# PWR.net
KiCad netlist of a schematic drawn in Altium Designer
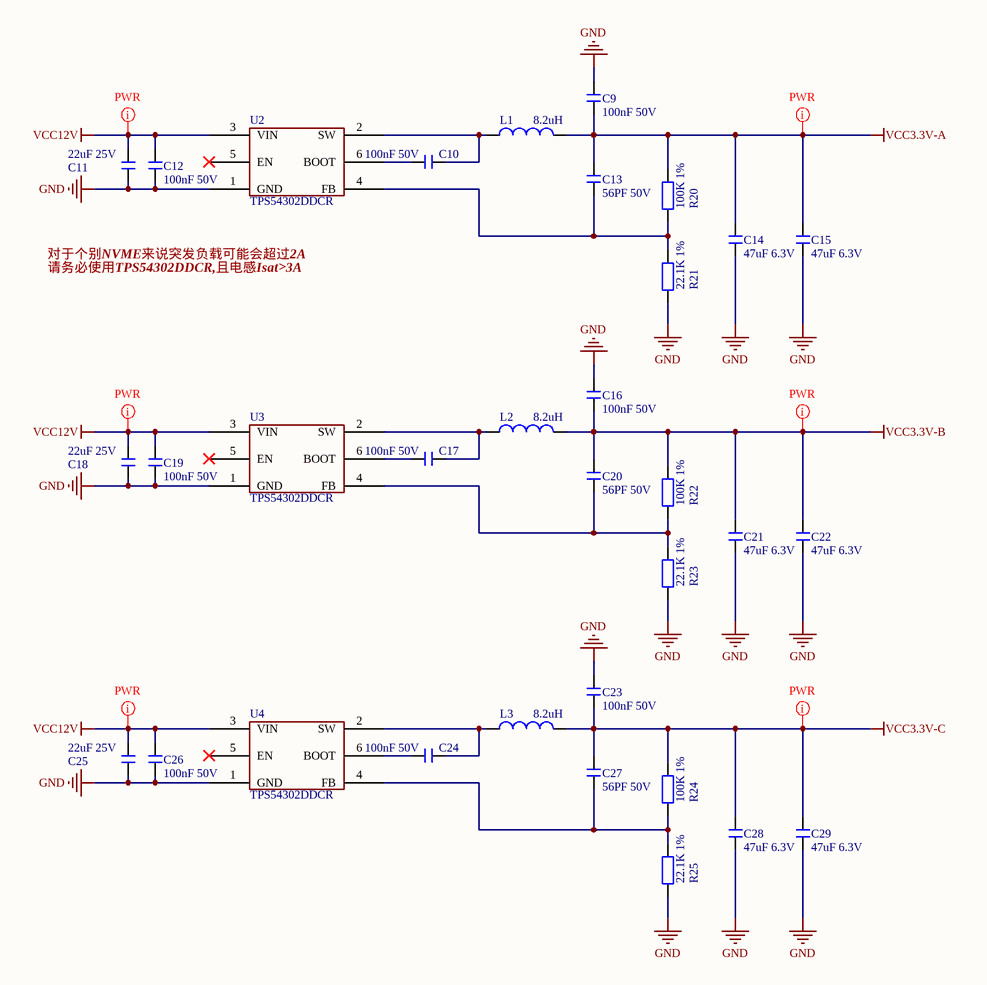
[diagram p0: PWR.SchDoc]

(export (version "E")
  (design (tool "Eeschema 10.0.6"))
  (components
    (comp (ref "C9")
      (value "100nF 50V")
      (footprint "C0402_L")
      (description "无极性贴片电容")
      (fields (field (name "版权归属") "源创客"))
      (libsource (lib "Capacitor") (part "C"))
    )
    (comp (ref "C10")
      (value "100nF 50V")
      (footprint "C0402_L")
      (description "无极性贴片电容")
      (fields (field (name "版权归属") "源创客"))
      (libsource (lib "Capacitor") (part "C"))
    )
    (comp (ref "C11")
      (value "22uF 25V")
      (footprint "C0805_L")
      (description "无极性贴片电容")
      (fields (field (name "版权归属") "源创客"))
      (libsource (lib "Capacitor") (part "C"))
    )
    (comp (ref "C12")
      (value "100nF 50V")
      (footprint "C0402_L")
      (description "无极性贴片电容")
      (fields (field (name "版权归属") "源创客"))
      (libsource (lib "Capacitor") (part "C"))
    )
    (comp (ref "C13")
      (value "56PF 50V")
      (footprint "C0402_L")
      (description "无极性贴片电容")
      (fields (field (name "版权归属") "源创客"))
      (libsource (lib "Capacitor") (part "C"))
    )
    (comp (ref "C14")
      (value "47uF 6.3V")
      (footprint "C0805_L")
      (description "无极性贴片电容")
      (fields (field (name "版权归属") "源创客"))
      (libsource (lib "Capacitor") (part "C"))
    )
    (comp (ref "C15")
      (value "47uF 6.3V")
      (footprint "C0805_L")
      (description "无极性贴片电容")
      (fields (field (name "版权归属") "源创客"))
      (libsource (lib "Capacitor") (part "C"))
    )
    (comp (ref "C16")
      (value "100nF 50V")
      (footprint "C0402_L")
      (description "无极性贴片电容")
      (fields (field (name "版权归属") "源创客"))
      (libsource (lib "Capacitor") (part "C"))
    )
    (comp (ref "C17")
      (value "100nF 50V")
      (footprint "C0402_L")
      (description "无极性贴片电容")
      (fields (field (name "版权归属") "源创客"))
      (libsource (lib "Capacitor") (part "C"))
    )
    (comp (ref "C18")
      (value "22uF 25V")
      (footprint "C0805_L")
      (description "无极性贴片电容")
      (fields (field (name "版权归属") "源创客"))
      (libsource (lib "Capacitor") (part "C"))
    )
    (comp (ref "C19")
      (value "100nF 50V")
      (footprint "C0402_L")
      (description "无极性贴片电容")
      (fields (field (name "版权归属") "源创客"))
      (libsource (lib "Capacitor") (part "C"))
    )
    (comp (ref "C20")
      (value "56PF 50V")
      (footprint "C0402_L")
      (description "无极性贴片电容")
      (fields (field (name "版权归属") "源创客"))
      (libsource (lib "Capacitor") (part "C"))
    )
    (comp (ref "C21")
      (value "47uF 6.3V")
      (footprint "C0805_L")
      (description "无极性贴片电容")
      (fields (field (name "版权归属") "源创客"))
      (libsource (lib "Capacitor") (part "C"))
    )
    (comp (ref "C22")
      (value "47uF 6.3V")
      (footprint "C0805_L")
      (description "无极性贴片电容")
      (fields (field (name "版权归属") "源创客"))
      (libsource (lib "Capacitor") (part "C"))
    )
    (comp (ref "C23")
      (value "100nF 50V")
      (footprint "C0402_L")
      (description "无极性贴片电容")
      (fields (field (name "版权归属") "源创客"))
      (libsource (lib "Capacitor") (part "C"))
    )
    (comp (ref "C24")
      (value "100nF 50V")
      (footprint "C0402_L")
      (description "无极性贴片电容")
      (fields (field (name "版权归属") "源创客"))
      (libsource (lib "Capacitor") (part "C"))
    )
    (comp (ref "C25")
      (value "22uF 25V")
      (footprint "C0805_L")
      (description "无极性贴片电容")
      (fields (field (name "版权归属") "源创客"))
      (libsource (lib "Capacitor") (part "C"))
    )
    (comp (ref "C26")
      (value "100nF 50V")
      (footprint "C0402_L")
      (description "无极性贴片电容")
      (fields (field (name "版权归属") "源创客"))
      (libsource (lib "Capacitor") (part "C"))
    )
    (comp (ref "C27")
      (value "56PF 50V")
      (footprint "C0402_L")
      (description "无极性贴片电容")
      (fields (field (name "版权归属") "源创客"))
      (libsource (lib "Capacitor") (part "C"))
    )
    (comp (ref "C28")
      (value "47uF 6.3V")
      (footprint "C0805_L")
      (description "无极性贴片电容")
      (fields (field (name "版权归属") "源创客"))
      (libsource (lib "Capacitor") (part "C"))
    )
    (comp (ref "C29")
      (value "47uF 6.3V")
      (footprint "C0805_L")
      (description "无极性贴片电容")
      (fields (field (name "版权归属") "源创客"))
      (libsource (lib "Capacitor") (part "C"))
    )
    (comp (ref "L1")
      (value "8.2uH")
      (footprint "L0630贴片电感")
      (description "小功率贴片电感")
      (fields (field (name "版权归属") "源创客"))
      (libsource (lib "Inductor") (part "L"))
    )
    (comp (ref "L2")
      (value "8.2uH")
      (footprint "L0630贴片电感")
      (description "小功率贴片电感")
      (fields (field (name "版权归属") "源创客"))
      (libsource (lib "Inductor") (part "L"))
    )
    (comp (ref "L3")
      (value "8.2uH")
      (footprint "L0630贴片电感")
      (description "小功率贴片电感")
      (fields (field (name "版权归属") "源创客"))
      (libsource (lib "Inductor") (part "L"))
    )
    (comp (ref "R20")
      (value "100K 1%")
      (footprint "R0402_L")
      (description "贴片电阻")
      (fields (field (name "版权归属") "源创客"))
      (libsource (lib "Resistor") (part "R"))
    )
    (comp (ref "R21")
      (value "22.1K 1%")
      (footprint "R0402_L")
      (description "贴片电阻")
      (fields (field (name "版权归属") "源创客"))
      (libsource (lib "Resistor") (part "R"))
    )
    (comp (ref "R22")
      (value "100K 1%")
      (footprint "R0402_L")
      (description "贴片电阻")
      (fields (field (name "版权归属") "源创客"))
      (libsource (lib "Resistor") (part "R"))
    )
    (comp (ref "R23")
      (value "22.1K 1%")
      (footprint "R0402_L")
      (description "贴片电阻")
      (fields (field (name "版权归属") "源创客"))
      (libsource (lib "Resistor") (part "R"))
    )
    (comp (ref "R24")
      (value "100K 1%")
      (footprint "R0402_L")
      (description "贴片电阻")
      (fields (field (name "版权归属") "源创客"))
      (libsource (lib "Resistor") (part "R"))
    )
    (comp (ref "R25")
      (value "22.1K 1%")
      (footprint "R0402_L")
      (description "贴片电阻")
      (fields (field (name "版权归属") "源创客"))
      (libsource (lib "Resistor") (part "R"))
    )
    (comp (ref "U2")
      (value "TPS54302DDCR")
      (footprint "SOT23-6L")
      (description "DCDC Convert")
      (libsource (lib "DCDC Convert") (part "TPS54202DDCR"))
    )
    (comp (ref "U3")
      (value "TPS54302DDCR")
      (footprint "SOT23-6L")
      (description "DCDC Convert")
      (libsource (lib "DCDC Convert") (part "TPS54202DDCR"))
    )
    (comp (ref "U4")
      (value "TPS54302DDCR")
      (footprint "SOT23-6L")
      (description "DCDC Convert")
      (libsource (lib "DCDC Convert") (part "TPS54202DDCR"))
    )
  )
  (nets
    (net (code "1") (name "GND") (class "Default")
      (node (ref "C11") (pin "1") (pinfunction "1_1") (pintype "passive"))
      (node (ref "C12") (pin "1") (pinfunction "1_1") (pintype "passive"))
      (node (ref "C14") (pin "2") (pinfunction "2_2") (pintype "passive"))
      (node (ref "C15") (pin "2") (pinfunction "2_2") (pintype "passive"))
      (node (ref "C16") (pin "2") (pinfunction "2_2") (pintype "passive"))
      (node (ref "C18") (pin "1") (pinfunction "1_1") (pintype "passive"))
      (node (ref "C19") (pin "1") (pinfunction "1_1") (pintype "passive"))
      (node (ref "C21") (pin "2") (pinfunction "2_2") (pintype "passive"))
      (node (ref "C22") (pin "2") (pinfunction "2_2") (pintype "passive"))
      (node (ref "C23") (pin "2") (pinfunction "2_2") (pintype "passive"))
      (node (ref "C25") (pin "1") (pinfunction "1_1") (pintype "passive"))
      (node (ref "C26") (pin "1") (pinfunction "1_1") (pintype "passive"))
      (node (ref "C28") (pin "2") (pinfunction "2_2") (pintype "passive"))
      (node (ref "C29") (pin "2") (pinfunction "2_2") (pintype "passive"))
      (node (ref "C9") (pin "2") (pinfunction "2_2") (pintype "passive"))
      (node (ref "R21") (pin "2") (pinfunction "2_2") (pintype "passive"))
      (node (ref "R23") (pin "2") (pinfunction "2_2") (pintype "passive"))
      (node (ref "R25") (pin "2") (pinfunction "2_2") (pintype "passive"))
      (node (ref "U2") (pin "1") (pinfunction "GND_1") (pintype "passive"))
      (node (ref "U3") (pin "1") (pinfunction "GND_1") (pintype "passive"))
      (node (ref "U4") (pin "1") (pinfunction "GND_1") (pintype "passive"))
    )
    (net (code "2") (name "Net-(U2-BOOT)") (class "Default")
      (node (ref "C10") (pin "1") (pinfunction "1_1") (pintype "passive"))
      (node (ref "U2") (pin "6") (pinfunction "BOOT_6") (pintype "passive"))
    )
    (net (code "3") (name "Net-(U2-FB)") (class "Default")
      (node (ref "C13") (pin "1") (pinfunction "1_1") (pintype "passive"))
      (node (ref "R20") (pin "2") (pinfunction "2_2") (pintype "passive"))
      (node (ref "R21") (pin "1") (pinfunction "1_1") (pintype "passive"))
      (node (ref "U2") (pin "4") (pinfunction "FB_4") (pintype "passive"))
    )
    (net (code "4") (name "Net-(U2-SW)") (class "Default")
      (node (ref "C10") (pin "2") (pinfunction "2_2") (pintype "passive"))
      (node (ref "L1") (pin "1") (pinfunction "1_1") (pintype "passive"))
      (node (ref "U2") (pin "2") (pinfunction "SW_2") (pintype "passive"))
    )
    (net (code "5") (name "Net-(U3-BOOT)") (class "Default")
      (node (ref "C17") (pin "1") (pinfunction "1_1") (pintype "passive"))
      (node (ref "U3") (pin "6") (pinfunction "BOOT_6") (pintype "passive"))
    )
    (net (code "6") (name "Net-(U3-FB)") (class "Default")
      (node (ref "C20") (pin "1") (pinfunction "1_1") (pintype "passive"))
      (node (ref "R22") (pin "2") (pinfunction "2_2") (pintype "passive"))
      (node (ref "R23") (pin "1") (pinfunction "1_1") (pintype "passive"))
      (node (ref "U3") (pin "4") (pinfunction "FB_4") (pintype "passive"))
    )
    (net (code "7") (name "Net-(U3-SW)") (class "Default")
      (node (ref "C17") (pin "2") (pinfunction "2_2") (pintype "passive"))
      (node (ref "L2") (pin "1") (pinfunction "1_1") (pintype "passive"))
      (node (ref "U3") (pin "2") (pinfunction "SW_2") (pintype "passive"))
    )
    (net (code "8") (name "Net-(U4-BOOT)") (class "Default")
      (node (ref "C24") (pin "1") (pinfunction "1_1") (pintype "passive"))
      (node (ref "U4") (pin "6") (pinfunction "BOOT_6") (pintype "passive"))
    )
    (net (code "9") (name "Net-(U4-FB)") (class "Default")
      (node (ref "C27") (pin "1") (pinfunction "1_1") (pintype "passive"))
      (node (ref "R24") (pin "2") (pinfunction "2_2") (pintype "passive"))
      (node (ref "R25") (pin "1") (pinfunction "1_1") (pintype "passive"))
      (node (ref "U4") (pin "4") (pinfunction "FB_4") (pintype "passive"))
    )
    (net (code "10") (name "Net-(U4-SW)") (class "Default")
      (node (ref "C24") (pin "2") (pinfunction "2_2") (pintype "passive"))
      (node (ref "L3") (pin "1") (pinfunction "1_1") (pintype "passive"))
      (node (ref "U4") (pin "2") (pinfunction "SW_2") (pintype "passive"))
    )
    (net (code "11") (name "VCC3.3V-A") (class "Default")
      (node (ref "C13") (pin "2") (pinfunction "2_2") (pintype "passive"))
      (node (ref "C14") (pin "1") (pinfunction "1_1") (pintype "passive"))
      (node (ref "C15") (pin "1") (pinfunction "1_1") (pintype "passive"))
      (node (ref "C9") (pin "1") (pinfunction "1_1") (pintype "passive"))
      (node (ref "L1") (pin "2") (pinfunction "2_2") (pintype "passive"))
      (node (ref "R20") (pin "1") (pinfunction "1_1") (pintype "passive"))
    )
    (net (code "12") (name "VCC3.3V-B") (class "Default")
      (node (ref "C16") (pin "1") (pinfunction "1_1") (pintype "passive"))
      (node (ref "C20") (pin "2") (pinfunction "2_2") (pintype "passive"))
      (node (ref "C21") (pin "1") (pinfunction "1_1") (pintype "passive"))
      (node (ref "C22") (pin "1") (pinfunction "1_1") (pintype "passive"))
      (node (ref "L2") (pin "2") (pinfunction "2_2") (pintype "passive"))
      (node (ref "R22") (pin "1") (pinfunction "1_1") (pintype "passive"))
    )
    (net (code "13") (name "VCC3.3V-C") (class "Default")
      (node (ref "C23") (pin "1") (pinfunction "1_1") (pintype "passive"))
      (node (ref "C27") (pin "2") (pinfunction "2_2") (pintype "passive"))
      (node (ref "C28") (pin "1") (pinfunction "1_1") (pintype "passive"))
      (node (ref "C29") (pin "1") (pinfunction "1_1") (pintype "passive"))
      (node (ref "L3") (pin "2") (pinfunction "2_2") (pintype "passive"))
      (node (ref "R24") (pin "1") (pinfunction "1_1") (pintype "passive"))
    )
    (net (code "14") (name "VCC12V") (class "Default")
      (node (ref "C11") (pin "2") (pinfunction "2_2") (pintype "passive"))
      (node (ref "C12") (pin "2") (pinfunction "2_2") (pintype "passive"))
      (node (ref "C18") (pin "2") (pinfunction "2_2") (pintype "passive"))
      (node (ref "C19") (pin "2") (pinfunction "2_2") (pintype "passive"))
      (node (ref "C25") (pin "2") (pinfunction "2_2") (pintype "passive"))
      (node (ref "C26") (pin "2") (pinfunction "2_2") (pintype "passive"))
      (node (ref "U2") (pin "3") (pinfunction "VIN_3") (pintype "passive"))
      (node (ref "U3") (pin "3") (pinfunction "VIN_3") (pintype "passive"))
      (node (ref "U4") (pin "3") (pinfunction "VIN_3") (pintype "passive"))
    )
    (net (code "15") (name "unconnected-(U2-EN-Pad5)") (class "Default")
      (node (ref "U2") (pin "5") (pinfunction "EN_5") (pintype "passive+no_connect"))
    )
    (net (code "16") (name "unconnected-(U3-EN-Pad5)") (class "Default")
      (node (ref "U3") (pin "5") (pinfunction "EN_5") (pintype "passive+no_connect"))
    )
    (net (code "17") (name "unconnected-(U4-EN-Pad5)") (class "Default")
      (node (ref "U4") (pin "5") (pinfunction "EN_5") (pintype "passive+no_connect"))
    )
  )
)
